# VoltageRegulator.net
KiCad netlist of a schematic drawn in Altium Designer
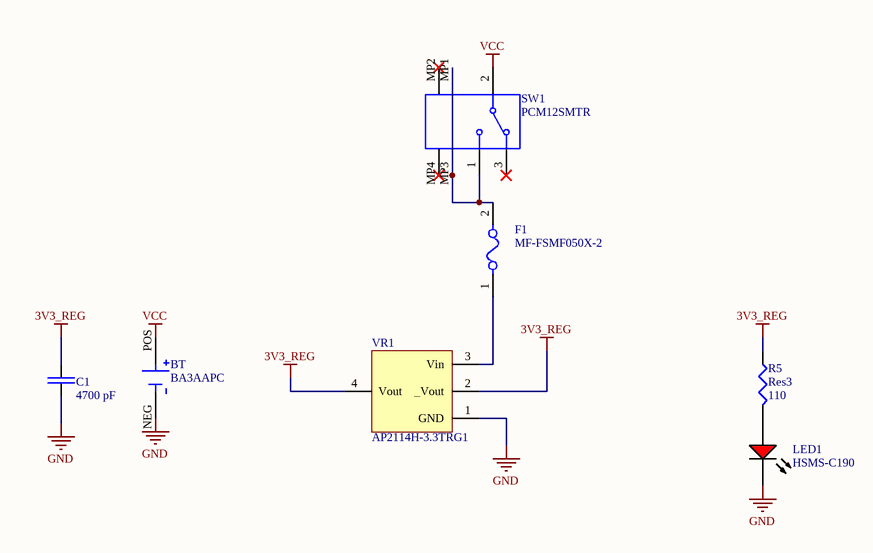
[diagram p0: VoltageRegulator.SchDoc]

(export (version "E")
  (design (tool "Eeschema 10.0.6"))
  (components
    (comp (ref "BT")
      (value "BA3AAPC")
      (footprint "BAT_BA3AAPC  Slimmed down")
      (description "Battery Holder _Open_ AA 3 Cell PC Pin")
      (fields
        (field (name "DIGI-KEY_PART_NUMBER") "BA3AAPC-ND")
        (field (name "MF") "MPD _Memory Protection Devices_")
      )
      (libsource (lib "BatteryHolder3AA") (part "BA3AAPC"))
    )
    (comp (ref "C1")
      (value "4700 pF")
      (footprint "4700uF 0805")
      (description "KEMET - C0805C472K5RACTU - CERAMIC CAPACITOR 4700PF, 50V, X7R, 10%, 0805")
      (fields (field (name "TOLERANCE") "10%") (field (name "VOLTAGE") "50V"))
      (libsource (lib "RSX_Capacitors") (part "4700pF 0805"))
    )
    (comp (ref "F1")
      (value "MF-FSMF050X-2")
      (footprint "FP-MF-FSMF-MFG")
      (description "PTC RESET FUSE 6V 500MA 0603")
      (fields
        (field (name "MANUFACTURER") "Bourns Inc.")
        (field (name "OCTOPART") "https://octopart.com/mf-fsmf050x-2-bourns-10470804")
      )
      (libsource (lib "Altium Content Vault") (part "5bcf9b9f640e542cf0359d10258e979"))
    )
    (comp (ref "LED1")
      (value "HSMS-C190")
      (footprint "AVAG-HSMX-C190_V")
      (description "LED Uni-Color Red, 52 mW, 20 mA, -40 to 85 degC, 2-Pin SMD, RoHS, Tape and Reel")
      (fields (field (name "MANUFACTURER") "Avago"))
      (libsource (lib "Altium Content Vault") (part "LED-RED-AK-2"))
    )
    (comp (ref "R5")
      (value "Res3")
      (footprint "RESC1608X06N_0603")
      (description "Resistor")
      (fields (field (name "ALTIUM_VALUE") "110") (field (name "PUBLISHER") "Altium Limited"))
      (libsource (lib "RSX_Resistors") (part "Res3"))
    )
    (comp (ref "SW1")
      (value "PCM12SMTR")
      (footprint "CKCP-PCM12SMTR_V")
      (description "Ultraminiature Slide Switch, SPDT, 0.3 A, 6 V, -20 to 85 degC, 3-Pin SMD, RoHS, Tape and Reel")
      (fields (field (name "MANUFACTURER") "C&K Components"))
      (libsource (lib "Altium Content Vault") (part "SW-SPDT-3_A"))
    )
    (comp (ref "VR1")
      (value "AP2114H-3.3TRG1")
      (footprint "AP2114")
      (libsource (lib "TXS2-L") (part "AP2114H-3.3TRG1"))
    )
  )
  (nets
    (net (code "1") (name "3V3_REG") (class "Default")
      (node (ref "C1") (pin "2") (pinfunction "16_2") (pintype "passive"))
      (node (ref "R5") (pin "1") (pinfunction "1_1") (pintype "passive"))
      (node (ref "VR1") (pin "2") (pinfunction "_Vout_2") (pintype "passive"))
      (node (ref "VR1") (pin "4") (pinfunction "Vout_4") (pintype "passive"))
    )
    (net (code "2") (name "GND") (class "Default")
      (node (ref "BT") (pin "NEG") (pinfunction "NEG_NEG") (pintype "passive"))
      (node (ref "C1") (pin "1") (pinfunction "15_1") (pintype "passive"))
      (node (ref "LED1") (pin "2") (pinfunction "K_2") (pintype "passive"))
      (node (ref "VR1") (pin "1") (pinfunction "GND_1") (pintype "passive"))
    )
    (net (code "3") (name "Net-(F1-Pad2)") (class "Default")
      (node (ref "F1") (pin "2") (pinfunction "2_2") (pintype "passive"))
      (node (ref "SW1") (pin "1") (pinfunction "1_1") (pintype "passive"))
      (node (ref "SW1") (pin "MP1") (pinfunction "MP1_MP1") (pintype "passive"))
      (node (ref "SW1") (pin "MP3") (pinfunction "MP3_MP3") (pintype "passive"))
    )
    (net (code "4") (name "Net-(LED1-A)") (class "Default")
      (node (ref "LED1") (pin "1") (pinfunction "A_1") (pintype "passive"))
      (node (ref "R5") (pin "2") (pinfunction "2_2") (pintype "passive"))
    )
    (net (code "5") (name "Net-(VR1-Vin)") (class "Default")
      (node (ref "F1") (pin "1") (pinfunction "1_1") (pintype "passive"))
      (node (ref "VR1") (pin "3") (pinfunction "Vin_3") (pintype "passive"))
    )
    (net (code "6") (name "VCC") (class "Default")
      (node (ref "BT") (pin "POS") (pinfunction "POS_POS") (pintype "passive"))
      (node (ref "SW1") (pin "2") (pinfunction "2_2") (pintype "passive"))
    )
    (net (code "7") (name "unconnected-(SW1-Pad3)") (class "Default")
      (node (ref "SW1") (pin "3") (pinfunction "3_3") (pintype "passive+no_connect"))
    )
    (net (code "8") (name "unconnected-(SW1-PadMP2)") (class "Default")
      (node (ref "SW1") (pin "MP2") (pinfunction "MP2_MP2") (pintype "passive+no_connect"))
    )
    (net (code "9") (name "unconnected-(SW1-PadMP4)") (class "Default")
      (node (ref "SW1") (pin "MP4") (pinfunction "MP4_MP4") (pintype "passive+no_connect"))
    )
  )
)
